# ODChannel.net
KiCad netlist of a schematic drawn in Altium Designer
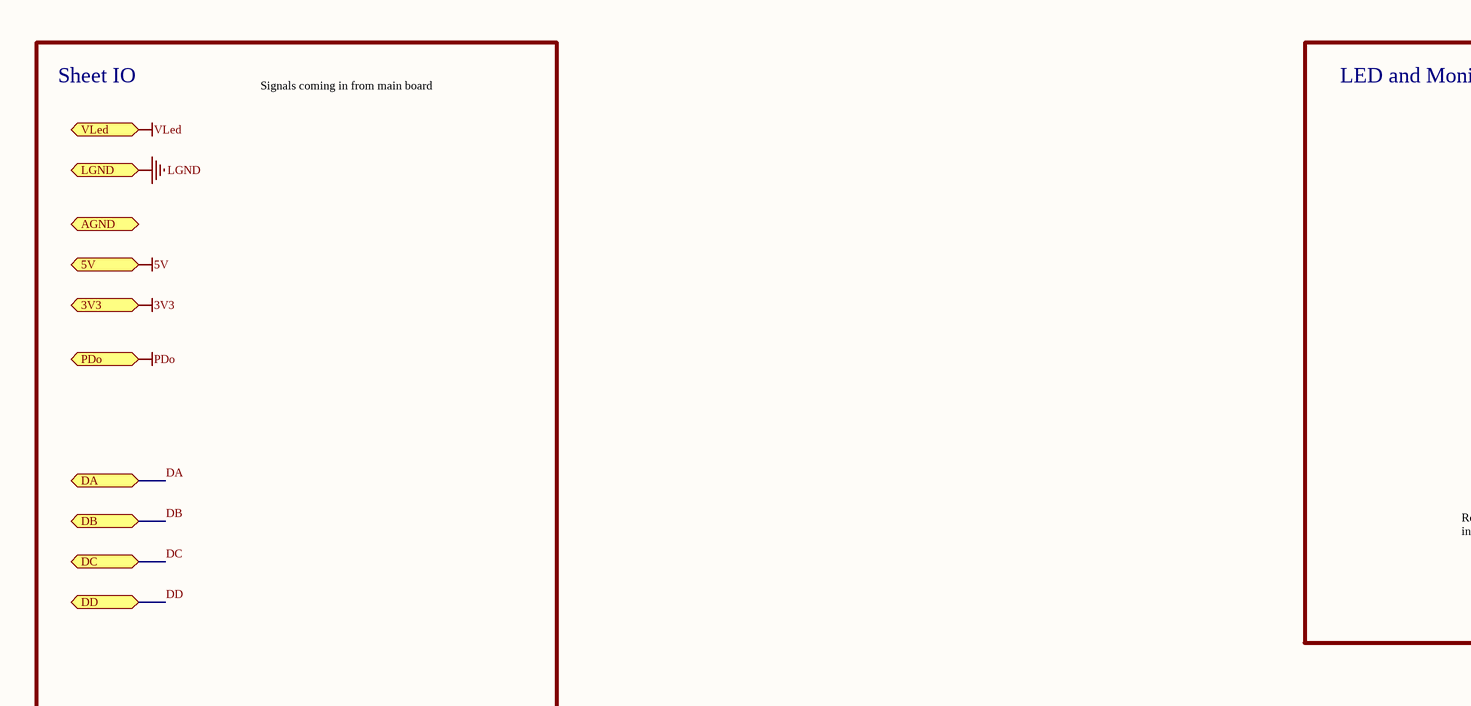
[diagram p0: ODChannel.SchDoc, left]
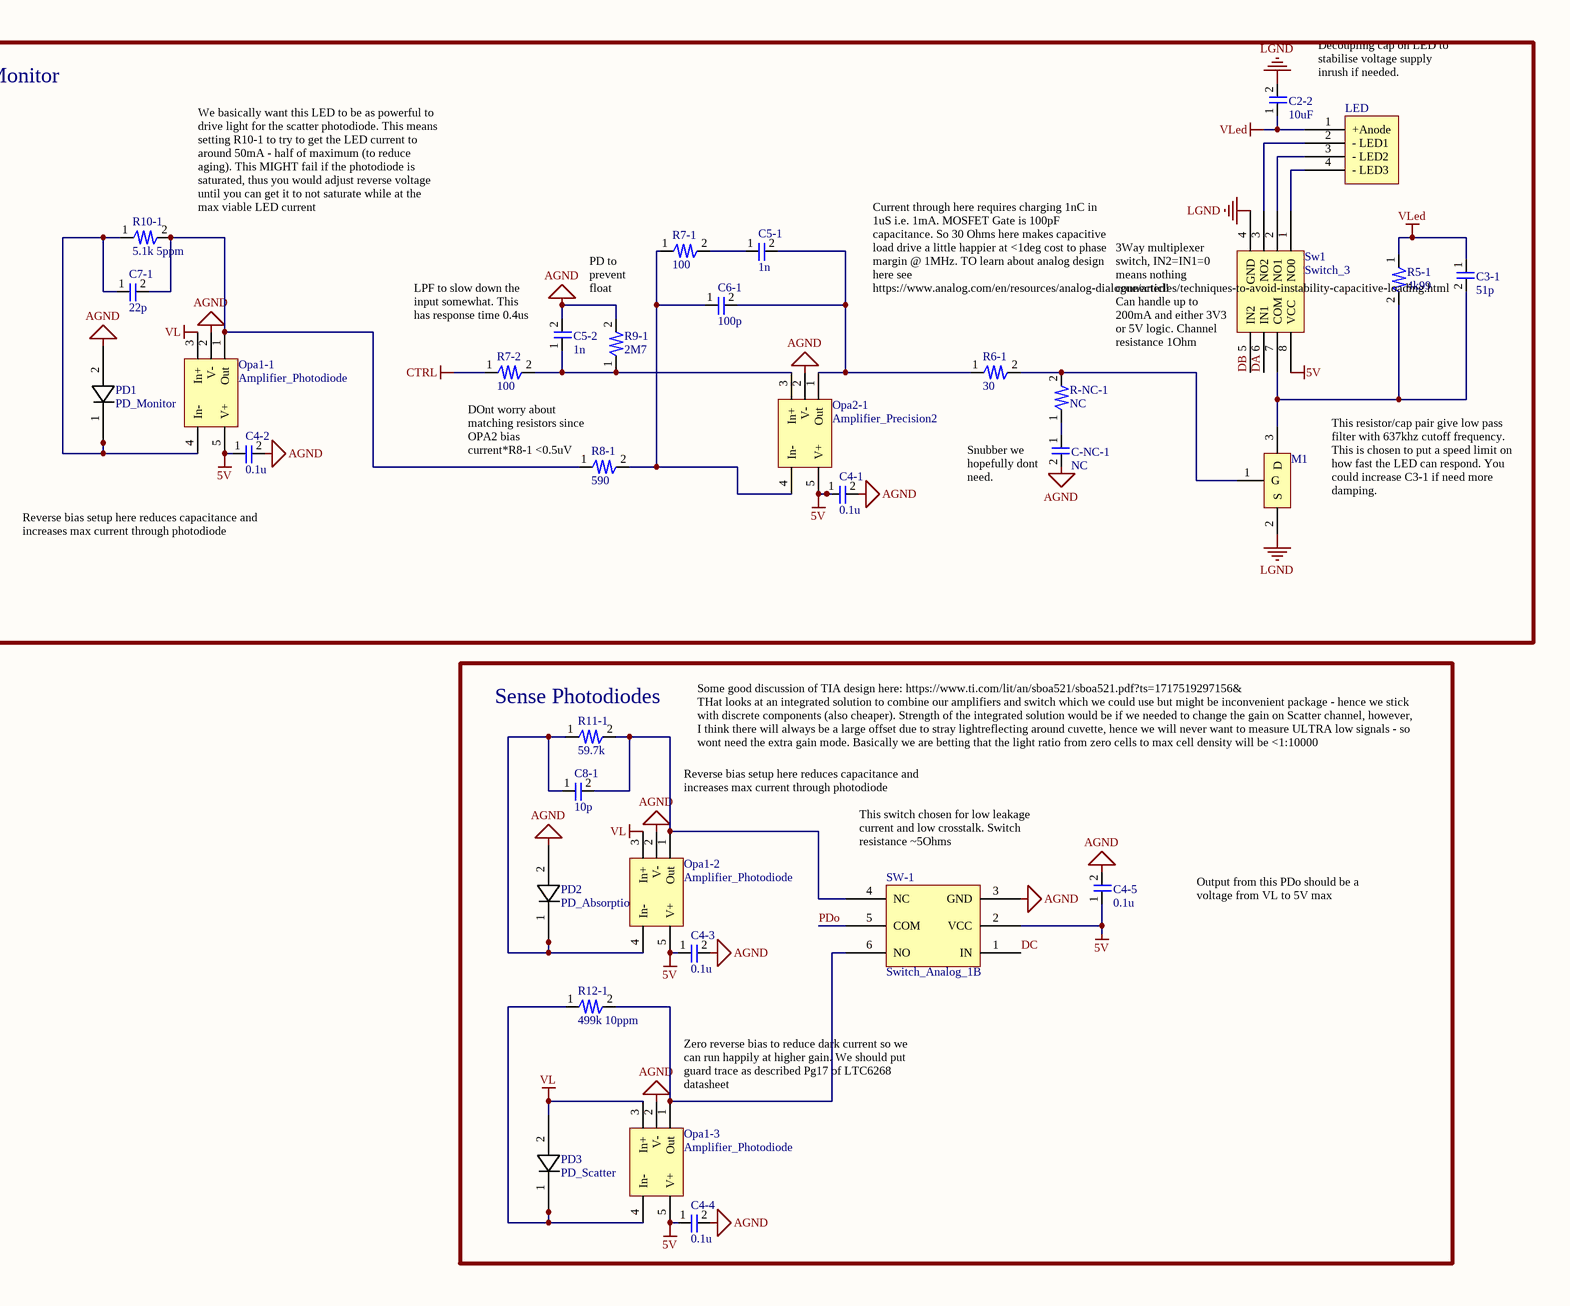
[diagram p1: ODChannel.SchDoc, right]

(export (version "E")
  (design (tool "Eeschema 10.0.6"))
  (components
    (comp (ref "C-NC-1")
      (value "NC")
      (footprint "0805")
      (libsource (lib "PCBSchematics") (part "Capacitor1"))
    )
    (comp (ref "C2-2")
      (value "10uF")
      (footprint "1206")
      (libsource (lib "PCBSchematics") (part "Capacitor1205"))
    )
    (comp (ref "C3-1") (value "51p") (footprint "0805") (libsource (lib "PCBSchematics") (part "Capacitor1")))
    (comp (ref "C4-1")
      (value "0.1u")
      (footprint "0805")
      (libsource (lib "PCBSchematics") (part "Capacitor1"))
    )
    (comp (ref "C4-2")
      (value "0.1u")
      (footprint "0805")
      (libsource (lib "PCBSchematics") (part "Capacitor1"))
    )
    (comp (ref "C4-3")
      (value "0.1u")
      (footprint "0805")
      (libsource (lib "PCBSchematics") (part "Capacitor1"))
    )
    (comp (ref "C4-4")
      (value "0.1u")
      (footprint "0805")
      (libsource (lib "PCBSchematics") (part "Capacitor1"))
    )
    (comp (ref "C4-5")
      (value "0.1u")
      (footprint "0805")
      (libsource (lib "PCBSchematics") (part "Capacitor1"))
    )
    (comp (ref "C5-1") (value "1n") (footprint "0805") (libsource (lib "PCBSchematics") (part "Capacitor1")))
    (comp (ref "C5-2") (value "1n") (footprint "0805") (libsource (lib "PCBSchematics") (part "Capacitor1")))
    (comp (ref "C6-1")
      (value "100p")
      (footprint "0805")
      (libsource (lib "PCBSchematics") (part "Capacitor1"))
    )
    (comp (ref "C7-1") (value "22p") (footprint "0805") (libsource (lib "PCBSchematics") (part "Capacitor1")))
    (comp (ref "C8-1") (value "10p") (footprint "0805") (libsource (lib "PCBSchematics") (part "Capacitor1")))
    (comp (ref "LED")
      (value "LEDx3 Header")
      (footprint "Header 2x2")
      (libsource (lib "PCBSchematics") (part "LEDx3 Header"))
    )
    (comp (ref "M1")
      (value "MOSFET-N_2")
      (footprint "SOT23-3")
      (libsource (lib "PCBSchematics") (part "MOSFET-N_2"))
    )
    (comp (ref "Opa1-1")
      (value "Amplifier_Photodiode")
      (footprint "SOT23-5")
      (libsource (lib "PCBSchematics") (part "Amplifier_Precision2"))
    )
    (comp (ref "Opa1-2")
      (value "Amplifier_Photodiode")
      (footprint "SOT23-5")
      (libsource (lib "PCBSchematics") (part "Amplifier_Precision2"))
    )
    (comp (ref "Opa1-3")
      (value "Amplifier_Photodiode")
      (footprint "SOT23-5")
      (libsource (lib "PCBSchematics") (part "Amplifier_Precision2"))
    )
    (comp (ref "Opa2-1")
      (value "Amplifier_Precision2")
      (footprint "SOT23-5")
      (libsource (lib "PCBSchematics") (part "Amplifier_Precision2"))
    )
    (comp (ref "PD1")
      (value "PD_Monitor")
      (footprint "Photodiode_S6967")
      (libsource (lib "PCBSchematics") (part "Photodiode_S6967"))
    )
    (comp (ref "PD2")
      (value "PD_Absorption")
      (footprint "Photodiode_S6967")
      (libsource (lib "PCBSchematics") (part "Photodiode_S6967"))
    )
    (comp (ref "PD3")
      (value "PD_Scatter")
      (footprint "Photodiode_S6967")
      (libsource (lib "PCBSchematics") (part "Photodiode_S6967"))
    )
    (comp (ref "R-NC-1") (value "NC") (footprint "0805") (libsource (lib "PCBSchematics") (part "Res1")))
    (comp (ref "R5-1") (value "4k99") (footprint "0805") (libsource (lib "PCBSchematics") (part "Res1")))
    (comp (ref "R6-1") (value "30") (footprint "0805") (libsource (lib "PCBSchematics") (part "Res1")))
    (comp (ref "R7-1") (value "100") (footprint "0805") (libsource (lib "PCBSchematics") (part "Res1")))
    (comp (ref "R7-2") (value "100") (footprint "0805") (libsource (lib "PCBSchematics") (part "Res1")))
    (comp (ref "R8-1") (value "590") (footprint "0805") (libsource (lib "PCBSchematics") (part "Res1")))
    (comp (ref "R9-1") (value "2M7") (footprint "0805") (libsource (lib "PCBSchematics") (part "Res1")))
    (comp (ref "R10-1")
      (value "5.1k 5ppm")
      (footprint "0805")
      (libsource (lib "PCBSchematics") (part "Res1"))
    )
    (comp (ref "R11-1") (value "59.7k") (footprint "0805") (libsource (lib "PCBSchematics") (part "Res1")))
    (comp (ref "R12-1")
      (value "499k 10ppm")
      (footprint "1206")
      (libsource (lib "PCBSchematics") (part "Res1"))
    )
    (comp (ref "SW-1")
      (value "Switch_Analog_1B")
      (footprint "6-TSSOP / SC-70-6")
      (libsource (lib "PCBSchematics") (part "Switch_Analog_1B"))
    )
    (comp (ref "Sw1")
      (value "Switch_3")
      (footprint "8-VSSOP")
      (libsource (lib "PCBSchematics") (part "Switch_3"))
    )
  )
  (nets
    (net (code "1") (name "/DA") (class "Default")
      (node (ref "Sw1") (pin "6") (pinfunction "IN1_6") (pintype "passive"))
    )
    (net (code "2") (name "/DB") (class "Default")
      (node (ref "Sw1") (pin "5") (pinfunction "IN2_5") (pintype "passive"))
    )
    (net (code "3") (name "/DC") (class "Default")
      (node (ref "SW-1") (pin "1") (pinfunction "IN_1") (pintype "passive"))
    )
    (net (code "6") (name "5V") (class "Default")
      (node (ref "C4-1") (pin "1") (pinfunction "1_1") (pintype "passive"))
      (node (ref "C4-2") (pin "1") (pinfunction "1_1") (pintype "passive"))
      (node (ref "C4-3") (pin "1") (pinfunction "1_1") (pintype "passive"))
      (node (ref "C4-4") (pin "1") (pinfunction "1_1") (pintype "passive"))
      (node (ref "C4-5") (pin "1") (pinfunction "1_1") (pintype "passive"))
      (node (ref "Opa1-1") (pin "5") (pinfunction "V+_5") (pintype "passive"))
      (node (ref "Opa1-2") (pin "5") (pinfunction "V+_5") (pintype "passive"))
      (node (ref "Opa1-3") (pin "5") (pinfunction "V+_5") (pintype "passive"))
      (node (ref "Opa2-1") (pin "5") (pinfunction "V+_5") (pintype "passive"))
      (node (ref "SW-1") (pin "2") (pinfunction "VCC_2") (pintype "passive"))
      (node (ref "Sw1") (pin "8") (pinfunction "VCC_8") (pintype "passive"))
    )
    (net (code "7") (name "AGND") (class "Default")
      (node (ref "C-NC-1") (pin "2") (pinfunction "2_2") (pintype "passive"))
      (node (ref "C4-1") (pin "2") (pinfunction "2_2") (pintype "passive"))
      (node (ref "C4-2") (pin "2") (pinfunction "2_2") (pintype "passive"))
      (node (ref "C4-3") (pin "2") (pinfunction "2_2") (pintype "passive"))
      (node (ref "C4-4") (pin "2") (pinfunction "2_2") (pintype "passive"))
      (node (ref "C4-5") (pin "2") (pinfunction "2_2") (pintype "passive"))
      (node (ref "C5-2") (pin "2") (pinfunction "2_2") (pintype "passive"))
      (node (ref "Opa1-1") (pin "2") (pinfunction "V-_2") (pintype "passive"))
      (node (ref "Opa1-2") (pin "2") (pinfunction "V-_2") (pintype "passive"))
      (node (ref "Opa1-3") (pin "2") (pinfunction "V-_2") (pintype "passive"))
      (node (ref "Opa2-1") (pin "2") (pinfunction "V-_2") (pintype "passive"))
      (node (ref "PD1") (pin "2") (pinfunction "2_2") (pintype "passive"))
      (node (ref "PD2") (pin "2") (pinfunction "2_2") (pintype "passive"))
      (node (ref "R9-1") (pin "2") (pinfunction "2_2") (pintype "passive"))
      (node (ref "SW-1") (pin "3") (pinfunction "GND_3") (pintype "passive"))
    )
    (net (code "8") (name "CTRL") (class "Default")
      (node (ref "R7-2") (pin "1") (pinfunction "1_1") (pintype "passive"))
    )
    (net (code "9") (name "LGND") (class "Default")
      (node (ref "C2-2") (pin "2") (pinfunction "2_2") (pintype "passive"))
      (node (ref "M1") (pin "2") (pinfunction "S_2") (pintype "passive"))
      (node (ref "Sw1") (pin "4") (pinfunction "GND_4") (pintype "passive"))
    )
    (net (code "10") (name "Net-(C-NC-1-Pad1)") (class "Default")
      (node (ref "C-NC-1") (pin "1") (pinfunction "1_1") (pintype "passive"))
      (node (ref "R-NC-1") (pin "1") (pinfunction "1_1") (pintype "passive"))
    )
    (net (code "11") (name "Net-(C5-1-Pad1)") (class "Default")
      (node (ref "C5-1") (pin "1") (pinfunction "1_1") (pintype "passive"))
      (node (ref "R7-1") (pin "2") (pinfunction "2_2") (pintype "passive"))
    )
    (net (code "12") (name "Net-(LED--_LED1)") (class "Default")
      (node (ref "LED") (pin "2") (pinfunction "-_LED1_2") (pintype "passive"))
      (node (ref "Sw1") (pin "3") (pinfunction "NO2_3") (pintype "passive"))
    )
    (net (code "13") (name "Net-(LED--_LED2)") (class "Default")
      (node (ref "LED") (pin "3") (pinfunction "-_LED2_3") (pintype "passive"))
      (node (ref "Sw1") (pin "2") (pinfunction "NO1_2") (pintype "passive"))
    )
    (net (code "14") (name "Net-(LED--_LED3)") (class "Default")
      (node (ref "LED") (pin "4") (pinfunction "-_LED3_4") (pintype "passive"))
      (node (ref "Sw1") (pin "1") (pinfunction "NO0_1") (pintype "passive"))
    )
    (net (code "15") (name "Net-(M1-D)") (class "Default")
      (node (ref "C3-1") (pin "2") (pinfunction "2_2") (pintype "passive"))
      (node (ref "M1") (pin "3") (pinfunction "D_3") (pintype "passive"))
      (node (ref "R5-1") (pin "2") (pinfunction "2_2") (pintype "passive"))
      (node (ref "Sw1") (pin "7") (pinfunction "COM_7") (pintype "passive"))
    )
    (net (code "16") (name "Net-(M1-G)") (class "Default")
      (node (ref "M1") (pin "1") (pinfunction "G_1") (pintype "passive"))
      (node (ref "R-NC-1") (pin "2") (pinfunction "2_2") (pintype "passive"))
      (node (ref "R6-1") (pin "2") (pinfunction "2_2") (pintype "passive"))
    )
    (net (code "17") (name "Net-(Opa1-1-In-)") (class "Default")
      (node (ref "C7-1") (pin "1") (pinfunction "1_1") (pintype "passive"))
      (node (ref "Opa1-1") (pin "4") (pinfunction "In-_4") (pintype "passive"))
      (node (ref "PD1") (pin "1") (pinfunction "1_1") (pintype "passive"))
      (node (ref "R10-1") (pin "1") (pinfunction "1_1") (pintype "passive"))
    )
    (net (code "18") (name "Net-(Opa1-1-Out)") (class "Default")
      (node (ref "C7-1") (pin "2") (pinfunction "2_2") (pintype "passive"))
      (node (ref "Opa1-1") (pin "1") (pinfunction "Out_1") (pintype "passive"))
      (node (ref "R10-1") (pin "2") (pinfunction "2_2") (pintype "passive"))
      (node (ref "R8-1") (pin "1") (pinfunction "1_1") (pintype "passive"))
    )
    (net (code "19") (name "Net-(Opa1-2-In-)") (class "Default")
      (node (ref "C8-1") (pin "1") (pinfunction "1_1") (pintype "passive"))
      (node (ref "Opa1-2") (pin "4") (pinfunction "In-_4") (pintype "passive"))
      (node (ref "PD2") (pin "1") (pinfunction "1_1") (pintype "passive"))
      (node (ref "R11-1") (pin "1") (pinfunction "1_1") (pintype "passive"))
    )
    (net (code "20") (name "Net-(Opa1-2-Out)") (class "Default")
      (node (ref "C8-1") (pin "2") (pinfunction "2_2") (pintype "passive"))
      (node (ref "Opa1-2") (pin "1") (pinfunction "Out_1") (pintype "passive"))
      (node (ref "R11-1") (pin "2") (pinfunction "2_2") (pintype "passive"))
      (node (ref "SW-1") (pin "4") (pinfunction "NC_4") (pintype "passive"))
    )
    (net (code "21") (name "Net-(Opa1-3-In-)") (class "Default")
      (node (ref "Opa1-3") (pin "4") (pinfunction "In-_4") (pintype "passive"))
      (node (ref "PD3") (pin "1") (pinfunction "1_1") (pintype "passive"))
      (node (ref "R12-1") (pin "1") (pinfunction "1_1") (pintype "passive"))
    )
    (net (code "22") (name "Net-(Opa1-3-Out)") (class "Default")
      (node (ref "Opa1-3") (pin "1") (pinfunction "Out_1") (pintype "passive"))
      (node (ref "R12-1") (pin "2") (pinfunction "2_2") (pintype "passive"))
      (node (ref "SW-1") (pin "6") (pinfunction "NO_6") (pintype "passive"))
    )
    (net (code "23") (name "Net-(Opa2-1-In+)") (class "Default")
      (node (ref "C5-2") (pin "1") (pinfunction "1_1") (pintype "passive"))
      (node (ref "Opa2-1") (pin "3") (pinfunction "In+_3") (pintype "passive"))
      (node (ref "R7-2") (pin "2") (pinfunction "2_2") (pintype "passive"))
      (node (ref "R9-1") (pin "1") (pinfunction "1_1") (pintype "passive"))
    )
    (net (code "24") (name "Net-(Opa2-1-In-)") (class "Default")
      (node (ref "C6-1") (pin "1") (pinfunction "1_1") (pintype "passive"))
      (node (ref "Opa2-1") (pin "4") (pinfunction "In-_4") (pintype "passive"))
      (node (ref "R7-1") (pin "1") (pinfunction "1_1") (pintype "passive"))
      (node (ref "R8-1") (pin "2") (pinfunction "2_2") (pintype "passive"))
    )
    (net (code "25") (name "Net-(Opa2-1-Out)") (class "Default")
      (node (ref "C5-1") (pin "2") (pinfunction "2_2") (pintype "passive"))
      (node (ref "C6-1") (pin "2") (pinfunction "2_2") (pintype "passive"))
      (node (ref "Opa2-1") (pin "1") (pinfunction "Out_1") (pintype "passive"))
      (node (ref "R6-1") (pin "1") (pinfunction "1_1") (pintype "passive"))
    )
    (net (code "26") (name "PDo") (class "Default")
      (node (ref "SW-1") (pin "5") (pinfunction "COM_5") (pintype "passive"))
    )
    (net (code "27") (name "VL") (class "Default")
      (node (ref "Opa1-1") (pin "3") (pinfunction "In+_3") (pintype "passive"))
      (node (ref "Opa1-2") (pin "3") (pinfunction "In+_3") (pintype "passive"))
      (node (ref "Opa1-3") (pin "3") (pinfunction "In+_3") (pintype "passive"))
      (node (ref "PD3") (pin "2") (pinfunction "2_2") (pintype "passive"))
    )
    (net (code "28") (name "VLed") (class "Default")
      (node (ref "C2-2") (pin "1") (pinfunction "1_1") (pintype "passive"))
      (node (ref "C3-1") (pin "1") (pinfunction "1_1") (pintype "passive"))
      (node (ref "LED") (pin "1") (pinfunction "+Anode_1") (pintype "passive"))
      (node (ref "R5-1") (pin "1") (pinfunction "1_1") (pintype "passive"))
    )
  )
)
